# Sheet1.net
KiCad netlist of a schematic drawn in Altium Designer
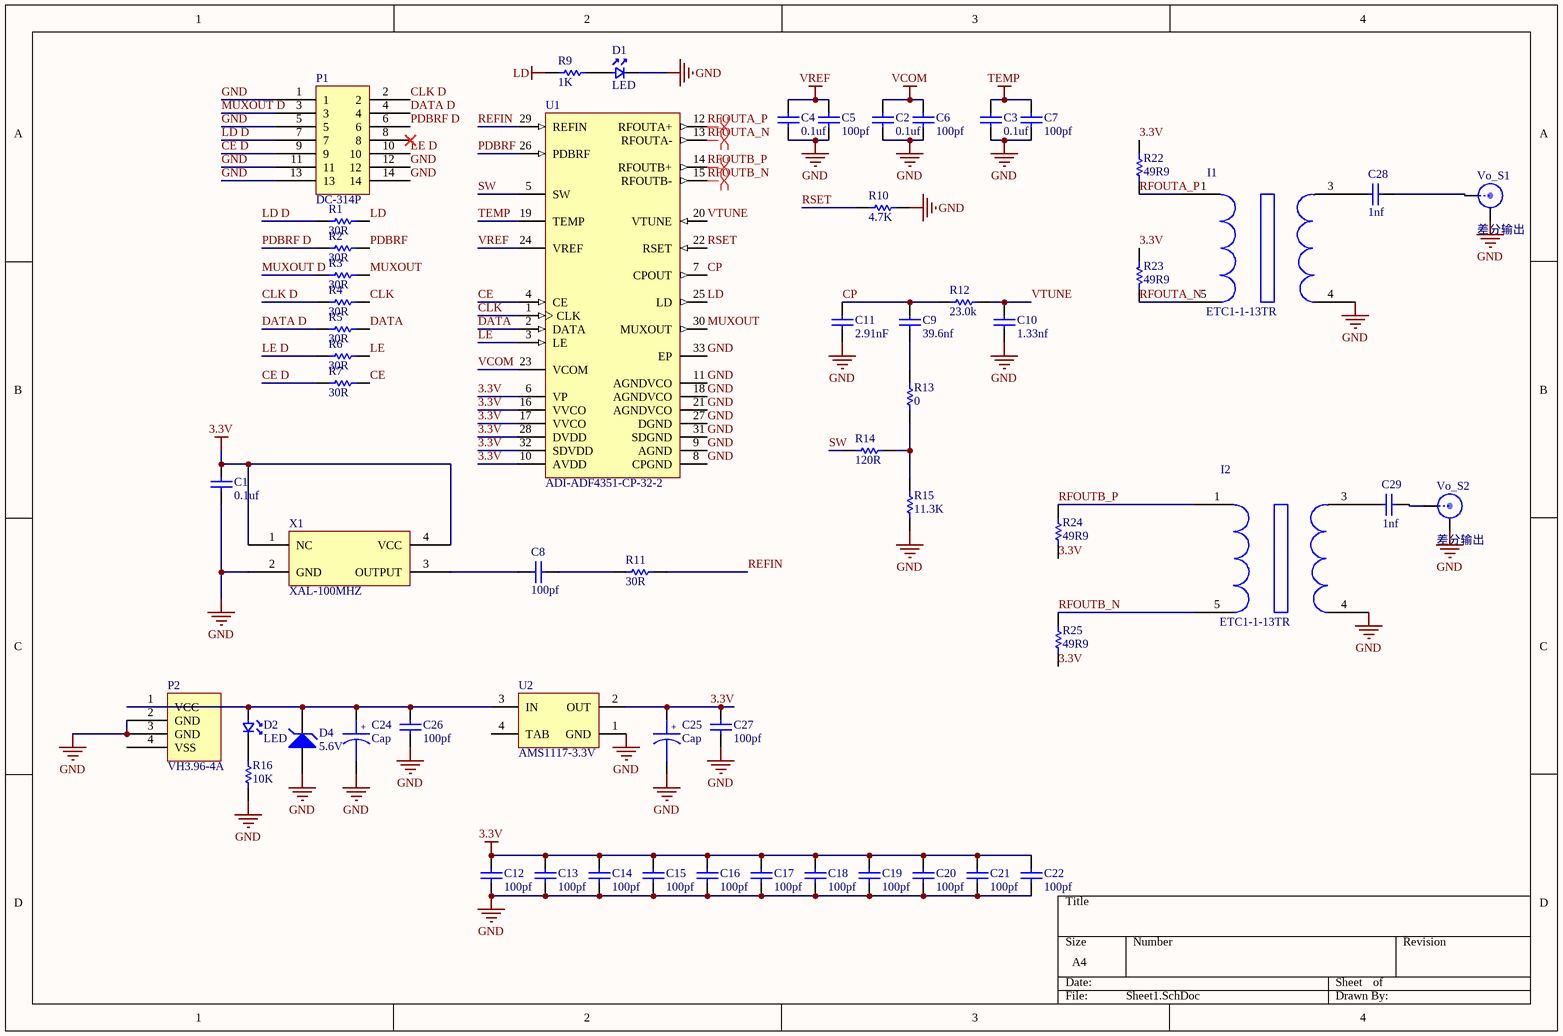
[diagram p0: Sheet1.SchDoc]

(export (version "E")
  (design (tool "Eeschema 10.0.6"))
  (components
    (comp (ref "C1") (value "0.1uf") (footprint "0805") (libsource (lib "Schlib1") (part "Cap")))
    (comp (ref "C2") (value "0.1uf") (footprint "0805") (libsource (lib "Schlib1") (part "Cap")))
    (comp (ref "C3") (value "0.1uf") (footprint "0805") (libsource (lib "Schlib1") (part "Cap")))
    (comp (ref "C4") (value "0.1uf") (footprint "0805") (libsource (lib "Schlib1") (part "Cap")))
    (comp (ref "C5") (value "100pf") (footprint "0805") (libsource (lib "Schlib1") (part "Cap")))
    (comp (ref "C6") (value "100pf") (footprint "0805") (libsource (lib "Schlib1") (part "Cap")))
    (comp (ref "C7") (value "100pf") (footprint "0805") (libsource (lib "Schlib1") (part "Cap")))
    (comp (ref "C8") (value "100pf") (footprint "0805") (libsource (lib "Schlib1") (part "Cap")))
    (comp (ref "C9") (value "39.6nf") (footprint "0805") (libsource (lib "Schlib1") (part "Cap")))
    (comp (ref "C10") (value "1.33nf") (footprint "0805") (libsource (lib "Schlib1") (part "Cap")))
    (comp (ref "C11") (value "2.91nF") (footprint "0805") (libsource (lib "Schlib1") (part "Cap")))
    (comp (ref "C12") (value "100pf") (footprint "0805") (libsource (lib "Schlib1") (part "Cap")))
    (comp (ref "C13") (value "100pf") (footprint "0805") (libsource (lib "Schlib1") (part "Cap")))
    (comp (ref "C14") (value "100pf") (footprint "0805") (libsource (lib "Schlib1") (part "Cap")))
    (comp (ref "C15") (value "100pf") (footprint "0805") (libsource (lib "Schlib1") (part "Cap")))
    (comp (ref "C16") (value "100pf") (footprint "0805") (libsource (lib "Schlib1") (part "Cap")))
    (comp (ref "C17") (value "100pf") (footprint "0805") (libsource (lib "Schlib1") (part "Cap")))
    (comp (ref "C18") (value "100pf") (footprint "0805") (libsource (lib "Schlib1") (part "Cap")))
    (comp (ref "C19") (value "100pf") (footprint "0805") (libsource (lib "Schlib1") (part "Cap")))
    (comp (ref "C20") (value "100pf") (footprint "0805") (libsource (lib "Schlib1") (part "Cap")))
    (comp (ref "C21") (value "100pf") (footprint "0805") (libsource (lib "Schlib1") (part "Cap")))
    (comp (ref "C22") (value "100pf") (footprint "0805") (libsource (lib "Schlib1") (part "Cap")))
    (comp (ref "C24")
      (value "Cap")
      (footprint "7343C-TYPE_D")
      (libsource (lib "Schlib1") (part "Tantalium Cap"))
    )
    (comp (ref "C25")
      (value "Cap")
      (footprint "7343C-TYPE_D")
      (libsource (lib "Schlib1") (part "Tantalium Cap"))
    )
    (comp (ref "C26") (value "100pf") (footprint "0805") (libsource (lib "Schlib1") (part "Cap")))
    (comp (ref "C27") (value "100pf") (footprint "0805") (libsource (lib "Schlib1") (part "Cap")))
    (comp (ref "C28") (value "1nf") (footprint "0805") (libsource (lib "Schlib1") (part "Cap")))
    (comp (ref "C29") (value "1nf") (footprint "0805") (libsource (lib "Schlib1") (part "Cap")))
    (comp (ref "D1") (value "LED") (footprint "0805_s") (libsource (lib "Schlib1") (part "LED")))
    (comp (ref "D2") (value "LED") (footprint "0805_s") (libsource (lib "Schlib1") (part "LED")))
    (comp (ref "D4") (value "5.6V") (footprint "SMA/DO-214AC") (libsource (lib "Schlib1") (part "肖特基-5.6V")))
    (comp (ref "I1")
      (value "ETC1-1-13TR")
      (footprint "SM-22")
      (libsource (lib "Schlib1") (part "ETC1-1-13TR"))
    )
    (comp (ref "I2")
      (value "ETC1-1-13TR")
      (footprint "SM-22")
      (libsource (lib "Schlib1") (part "ETC1-1-13TR"))
    )
    (comp (ref "P1") (value "DC-314P") (footprint "DC3-14P") (libsource (lib "Schlib1") (part "DC3-14P")))
    (comp (ref "P2")
      (value "VH3.96-4A")
      (footprint "VH3.96-4P")
      (libsource (lib "Schlib1") (part "VH3.96-4A"))
    )
    (comp (ref "R1") (value "30R") (footprint "0805") (libsource (lib "Schlib1") (part "Res")))
    (comp (ref "R2") (value "30R") (footprint "0805") (libsource (lib "Schlib1") (part "Res")))
    (comp (ref "R3") (value "30R") (footprint "0805") (libsource (lib "Schlib1") (part "Res")))
    (comp (ref "R4") (value "30R") (footprint "0805") (libsource (lib "Schlib1") (part "Res")))
    (comp (ref "R5") (value "30R") (footprint "0805") (libsource (lib "Schlib1") (part "Res")))
    (comp (ref "R6") (value "30R") (footprint "0805") (libsource (lib "Schlib1") (part "Res")))
    (comp (ref "R7") (value "30R") (footprint "0805") (libsource (lib "Schlib1") (part "Res")))
    (comp (ref "R9") (value "1K") (footprint "0805") (libsource (lib "Schlib1") (part "Res")))
    (comp (ref "R10") (value "4.7K") (footprint "0805") (libsource (lib "Schlib1") (part "Res")))
    (comp (ref "R11") (value "30R") (footprint "0805") (libsource (lib "Schlib1") (part "Res")))
    (comp (ref "R12") (value "23.0k") (footprint "0805") (libsource (lib "Schlib1") (part "Res")))
    (comp (ref "R13") (value "0") (footprint "0805") (libsource (lib "Schlib1") (part "Res")))
    (comp (ref "R14") (value "120R") (footprint "0805") (libsource (lib "Schlib1") (part "Res")))
    (comp (ref "R15") (value "11.3K") (footprint "0805") (libsource (lib "Schlib1") (part "Res")))
    (comp (ref "R16") (value "10K") (footprint "0805") (libsource (lib "Schlib1") (part "Res")))
    (comp (ref "R22") (value "49R9") (footprint "0805") (libsource (lib "Schlib1") (part "Res")))
    (comp (ref "R23") (value "49R9") (footprint "0805") (libsource (lib "Schlib1") (part "Res")))
    (comp (ref "R24") (value "49R9") (footprint "0805") (libsource (lib "Schlib1") (part "Res")))
    (comp (ref "R25") (value "49R9") (footprint "0805") (libsource (lib "Schlib1") (part "Res")))
    (comp (ref "U1")
      (value "ADI-ADF4351-CP-32-2")
      (footprint "ADI-CP-32-2_M")
      (libsource (lib "Schlib1") (part "ADI-ADF4351-CP-32-2"))
    )
    (comp (ref "U2")
      (value "AMS1117-3.3V")
      (footprint "SOT-223")
      (libsource (lib "Schlib1") (part "AMS1117-3.3V"))
    )
    (comp (ref "Vo_S1") (value "差分输出") (footprint "SMA-LYING") (libsource (lib "Schlib1") (part "SMA")))
    (comp (ref "Vo_S2") (value "差分输出") (footprint "SMA-LYING") (libsource (lib "Schlib1") (part "SMA")))
    (comp (ref "X1") (value "XAL-100MHZ") (footprint "SMD4_7050") (libsource (lib "Schlib1") (part "XAL")))
  )
  (nets
    (net (code "1") (name "/CE") (class "Default")
      (node (ref "R7") (pin "2") (pinfunction "2_2") (pintype "passive"))
      (node (ref "U1") (pin "4") (pinfunction "CE_4") (pintype "input"))
    )
    (net (code "2") (name "/CE D") (class "Default")
      (node (ref "P1") (pin "9") (pinfunction "9_9") (pintype "passive"))
      (node (ref "R7") (pin "1") (pinfunction "1_1") (pintype "passive"))
    )
    (net (code "3") (name "/CLK") (class "Default")
      (node (ref "R4") (pin "2") (pinfunction "2_2") (pintype "passive"))
      (node (ref "U1") (pin "1") (pinfunction "CLK_1") (pintype "input"))
    )
    (net (code "4") (name "/CLK D") (class "Default")
      (node (ref "P1") (pin "2") (pinfunction "2_2") (pintype "passive"))
      (node (ref "R4") (pin "1") (pinfunction "1_1") (pintype "passive"))
    )
    (net (code "5") (name "/CP") (class "Default")
      (node (ref "C11") (pin "2") (pinfunction "2_2") (pintype "passive"))
      (node (ref "C9") (pin "2") (pinfunction "2_2") (pintype "passive"))
      (node (ref "R12") (pin "1") (pinfunction "1_1") (pintype "passive"))
      (node (ref "U1") (pin "7") (pinfunction "CPOUT_7") (pintype "output"))
    )
    (net (code "6") (name "/DATA") (class "Default")
      (node (ref "R5") (pin "2") (pinfunction "2_2") (pintype "passive"))
      (node (ref "U1") (pin "2") (pinfunction "DATA_2") (pintype "input"))
    )
    (net (code "7") (name "/DATA D") (class "Default")
      (node (ref "P1") (pin "4") (pinfunction "4_4") (pintype "passive"))
      (node (ref "R5") (pin "1") (pinfunction "1_1") (pintype "passive"))
    )
    (net (code "8") (name "/LD D") (class "Default")
      (node (ref "P1") (pin "7") (pinfunction "7_7") (pintype "passive"))
      (node (ref "R1") (pin "1") (pinfunction "1_1") (pintype "passive"))
    )
    (net (code "9") (name "/LE") (class "Default")
      (node (ref "R6") (pin "2") (pinfunction "2_2") (pintype "passive"))
      (node (ref "U1") (pin "3") (pinfunction "LE_3") (pintype "input"))
    )
    (net (code "10") (name "/LE D") (class "Default")
      (node (ref "P1") (pin "10") (pinfunction "10_10") (pintype "passive"))
      (node (ref "R6") (pin "1") (pinfunction "1_1") (pintype "passive"))
    )
    (net (code "11") (name "/MUXOUT") (class "Default")
      (node (ref "R3") (pin "2") (pinfunction "2_2") (pintype "passive"))
      (node (ref "U1") (pin "30") (pinfunction "MUXOUT_30") (pintype "output"))
    )
    (net (code "12") (name "/MUXOUT D") (class "Default")
      (node (ref "P1") (pin "3") (pinfunction "3_3") (pintype "passive"))
      (node (ref "R3") (pin "1") (pinfunction "1_1") (pintype "passive"))
    )
    (net (code "13") (name "/PDBRF") (class "Default")
      (node (ref "R2") (pin "2") (pinfunction "2_2") (pintype "passive"))
      (node (ref "U1") (pin "26") (pinfunction "PDBRF_26") (pintype "input"))
    )
    (net (code "14") (name "/PDBRF D") (class "Default")
      (node (ref "P1") (pin "6") (pinfunction "6_6") (pintype "passive"))
      (node (ref "R2") (pin "1") (pinfunction "1_1") (pintype "passive"))
    )
    (net (code "15") (name "/REFIN") (class "Default")
      (node (ref "R11") (pin "1") (pinfunction "1_1") (pintype "passive"))
      (node (ref "U1") (pin "29") (pinfunction "REFIN_29") (pintype "input"))
    )
    (net (code "16") (name "/RFOUTA_N") (class "Default")
      (node (ref "I1") (pin "5") (pinfunction "5_5") (pintype "passive"))
      (node (ref "R23") (pin "2") (pinfunction "2_2") (pintype "passive"))
      (node (ref "U1") (pin "13") (pinfunction "RFOUTA-_13") (pintype "output"))
    )
    (net (code "17") (name "/RFOUTA_P") (class "Default")
      (node (ref "I1") (pin "1") (pinfunction "1_1") (pintype "passive"))
      (node (ref "R22") (pin "1") (pinfunction "1_1") (pintype "passive"))
      (node (ref "U1") (pin "12") (pinfunction "RFOUTA+_12") (pintype "output"))
    )
    (net (code "18") (name "/RFOUTB_N") (class "Default")
      (node (ref "I2") (pin "5") (pinfunction "5_5") (pintype "passive"))
      (node (ref "R25") (pin "2") (pinfunction "2_2") (pintype "passive"))
      (node (ref "U1") (pin "15") (pinfunction "RFOUTB-_15") (pintype "output"))
    )
    (net (code "19") (name "/RFOUTB_P") (class "Default")
      (node (ref "I2") (pin "1") (pinfunction "1_1") (pintype "passive"))
      (node (ref "R24") (pin "2") (pinfunction "2_2") (pintype "passive"))
      (node (ref "U1") (pin "14") (pinfunction "RFOUTB+_14") (pintype "output"))
    )
    (net (code "20") (name "/RSET") (class "Default")
      (node (ref "R10") (pin "1") (pinfunction "1_1") (pintype "passive"))
      (node (ref "U1") (pin "22") (pinfunction "RSET_22") (pintype "input"))
    )
    (net (code "21") (name "/SW") (class "Default")
      (node (ref "R14") (pin "2") (pinfunction "2_2") (pintype "passive"))
      (node (ref "U1") (pin "5") (pinfunction "SW_5") (pintype "passive"))
    )
    (net (code "22") (name "/VTUNE") (class "Default")
      (node (ref "C10") (pin "2") (pinfunction "2_2") (pintype "passive"))
      (node (ref "R12") (pin "2") (pinfunction "2_2") (pintype "passive"))
      (node (ref "U1") (pin "20") (pinfunction "VTUNE_20") (pintype "input"))
    )
    (net (code "23") (name "3.3V") (class "Default")
      (node (ref "C1") (pin "2") (pinfunction "2_2") (pintype "passive"))
      (node (ref "C12") (pin "2") (pinfunction "2_2") (pintype "passive"))
      (node (ref "C13") (pin "2") (pinfunction "2_2") (pintype "passive"))
      (node (ref "C14") (pin "2") (pinfunction "2_2") (pintype "passive"))
      (node (ref "C15") (pin "2") (pinfunction "2_2") (pintype "passive"))
      (node (ref "C16") (pin "2") (pinfunction "2_2") (pintype "passive"))
      (node (ref "C17") (pin "2") (pinfunction "2_2") (pintype "passive"))
      (node (ref "C18") (pin "2") (pinfunction "2_2") (pintype "passive"))
      (node (ref "C19") (pin "2") (pinfunction "2_2") (pintype "passive"))
      (node (ref "C20") (pin "2") (pinfunction "2_2") (pintype "passive"))
      (node (ref "C21") (pin "2") (pinfunction "2_2") (pintype "passive"))
      (node (ref "C22") (pin "2") (pinfunction "2_2") (pintype "passive"))
      (node (ref "C25") (pin "1") (pinfunction "1_1") (pintype "passive"))
      (node (ref "C27") (pin "2") (pinfunction "2_2") (pintype "passive"))
      (node (ref "R22") (pin "2") (pinfunction "2_2") (pintype "passive"))
      (node (ref "R23") (pin "1") (pinfunction "1_1") (pintype "passive"))
      (node (ref "R24") (pin "1") (pinfunction "1_1") (pintype "passive"))
      (node (ref "R25") (pin "1") (pinfunction "1_1") (pintype "passive"))
      (node (ref "U1") (pin "10") (pinfunction "AVDD_10") (pintype "power_in"))
      (node (ref "U1") (pin "16") (pinfunction "VVCO_16") (pintype "power_in"))
      (node (ref "U1") (pin "17") (pinfunction "VVCO_17") (pintype "power_in"))
      (node (ref "U1") (pin "28") (pinfunction "DVDD_28") (pintype "power_in"))
      (node (ref "U1") (pin "32") (pinfunction "SDVDD_32") (pintype "power_in"))
      (node (ref "U1") (pin "6") (pinfunction "VP_6") (pintype "power_in"))
      (node (ref "U2") (pin "2") (pinfunction "OUT_2") (pintype "power_in"))
      (node (ref "X1") (pin "1") (pinfunction "NC_1") (pintype "passive"))
      (node (ref "X1") (pin "4") (pinfunction "VCC_4") (pintype "passive"))
    )
    (net (code "24") (name "GND") (class "Default")
      (node (ref "C1") (pin "1") (pinfunction "1_1") (pintype "passive"))
      (node (ref "C10") (pin "1") (pinfunction "1_1") (pintype "passive"))
      (node (ref "C11") (pin "1") (pinfunction "1_1") (pintype "passive"))
      (node (ref "C12") (pin "1") (pinfunction "1_1") (pintype "passive"))
      (node (ref "C13") (pin "1") (pinfunction "1_1") (pintype "passive"))
      (node (ref "C14") (pin "1") (pinfunction "1_1") (pintype "passive"))
      (node (ref "C15") (pin "1") (pinfunction "1_1") (pintype "passive"))
      (node (ref "C16") (pin "1") (pinfunction "1_1") (pintype "passive"))
      (node (ref "C17") (pin "1") (pinfunction "1_1") (pintype "passive"))
      (node (ref "C18") (pin "1") (pinfunction "1_1") (pintype "passive"))
      (node (ref "C19") (pin "1") (pinfunction "1_1") (pintype "passive"))
      (node (ref "C2") (pin "1") (pinfunction "1_1") (pintype "passive"))
      (node (ref "C20") (pin "1") (pinfunction "1_1") (pintype "passive"))
      (node (ref "C21") (pin "1") (pinfunction "1_1") (pintype "passive"))
      (node (ref "C22") (pin "1") (pinfunction "1_1") (pintype "passive"))
      (node (ref "C24") (pin "2") (pinfunction "2_2") (pintype "passive"))
      (node (ref "C25") (pin "2") (pinfunction "2_2") (pintype "passive"))
      (node (ref "C26") (pin "1") (pinfunction "1_1") (pintype "passive"))
      (node (ref "C27") (pin "1") (pinfunction "1_1") (pintype "passive"))
      (node (ref "C3") (pin "1") (pinfunction "1_1") (pintype "passive"))
      (node (ref "C4") (pin "1") (pinfunction "1_1") (pintype "passive"))
      (node (ref "C5") (pin "1") (pinfunction "1_1") (pintype "passive"))
      (node (ref "C6") (pin "1") (pinfunction "1_1") (pintype "passive"))
      (node (ref "C7") (pin "1") (pinfunction "1_1") (pintype "passive"))
      (node (ref "D1") (pin "1") (pinfunction "1_1") (pintype "passive"))
      (node (ref "D4") (pin "1") (pinfunction "A_1") (pintype "passive"))
      (node (ref "I1") (pin "4") (pinfunction "4_4") (pintype "passive"))
      (node (ref "I2") (pin "4") (pinfunction "4_4") (pintype "passive"))
      (node (ref "P1") (pin "1") (pinfunction "1_1") (pintype "passive"))
      (node (ref "P1") (pin "11") (pinfunction "11_11") (pintype "passive"))
      (node (ref "P1") (pin "12") (pinfunction "12_12") (pintype "passive"))
      (node (ref "P1") (pin "13") (pinfunction "13_13") (pintype "passive"))
      (node (ref "P1") (pin "14") (pinfunction "14_14") (pintype "passive"))
      (node (ref "P1") (pin "5") (pinfunction "5_5") (pintype "passive"))
      (node (ref "P2") (pin "2") (pinfunction "GND_2") (pintype "passive"))
      (node (ref "P2") (pin "3") (pinfunction "GND_3") (pintype "passive"))
      (node (ref "R10") (pin "2") (pinfunction "2_2") (pintype "passive"))
      (node (ref "R15") (pin "2") (pinfunction "2_2") (pintype "passive"))
      (node (ref "R16") (pin "1") (pinfunction "1_1") (pintype "passive"))
      (node (ref "U1") (pin "11") (pinfunction "AGNDVCO_11") (pintype "power_in"))
      (node (ref "U1") (pin "18") (pinfunction "AGNDVCO_18") (pintype "power_in"))
      (node (ref "U1") (pin "21") (pinfunction "AGNDVCO_21") (pintype "power_in"))
      (node (ref "U1") (pin "27") (pinfunction "DGND_27") (pintype "power_in"))
      (node (ref "U1") (pin "31") (pinfunction "SDGND_31") (pintype "power_in"))
      (node (ref "U1") (pin "33") (pinfunction "EP_33") (pintype "power_in"))
      (node (ref "U1") (pin "8") (pinfunction "CPGND_8") (pintype "power_in"))
      (node (ref "U1") (pin "9") (pinfunction "AGND_9") (pintype "power_in"))
      (node (ref "U2") (pin "1") (pinfunction "GND_1") (pintype "power_in"))
      (node (ref "Vo_S1") (pin "1") (pinfunction "1_1") (pintype "passive"))
      (node (ref "Vo_S2") (pin "1") (pinfunction "1_1") (pintype "passive"))
      (node (ref "X1") (pin "2") (pinfunction "GND_2") (pintype "passive"))
    )
    (net (code "25") (name "LD") (class "Default")
      (node (ref "R1") (pin "2") (pinfunction "2_2") (pintype "passive"))
      (node (ref "R9") (pin "1") (pinfunction "1_1") (pintype "passive"))
      (node (ref "U1") (pin "25") (pinfunction "LD_25") (pintype "output"))
    )
    (net (code "26") (name "Net-(C8-Pad1)") (class "Default")
      (node (ref "C8") (pin "1") (pinfunction "1_1") (pintype "passive"))
      (node (ref "R11") (pin "2") (pinfunction "2_2") (pintype "passive"))
    )
    (net (code "27") (name "Net-(C9-Pad1)") (class "Default")
      (node (ref "C9") (pin "1") (pinfunction "1_1") (pintype "passive"))
      (node (ref "R13") (pin "2") (pinfunction "2_2") (pintype "passive"))
    )
    (net (code "28") (name "Net-(C28-Pad1)") (class "Default")
      (node (ref "C28") (pin "1") (pinfunction "1_1") (pintype "passive"))
      (node (ref "I1") (pin "3") (pinfunction "3_3") (pintype "passive"))
    )
    (net (code "29") (name "Net-(C28-Pad2)") (class "Default")
      (node (ref "C28") (pin "2") (pinfunction "2_2") (pintype "passive"))
      (node (ref "Vo_S1") (pin "0") (pinfunction "0_0") (pintype "passive"))
    )
    (net (code "30") (name "Net-(C29-Pad1)") (class "Default")
      (node (ref "C29") (pin "1") (pinfunction "1_1") (pintype "passive"))
      (node (ref "I2") (pin "3") (pinfunction "3_3") (pintype "passive"))
    )
    (net (code "31") (name "Net-(C29-Pad2)") (class "Default")
      (node (ref "C29") (pin "2") (pinfunction "2_2") (pintype "passive"))
      (node (ref "Vo_S2") (pin "0") (pinfunction "0_0") (pintype "passive"))
    )
    (net (code "32") (name "Net-(D1-Pad2)") (class "Default")
      (node (ref "D1") (pin "2") (pinfunction "2_2") (pintype "passive"))
      (node (ref "R9") (pin "2") (pinfunction "2_2") (pintype "passive"))
    )
    (net (code "33") (name "Net-(D2-Pad1)") (class "Default")
      (node (ref "D2") (pin "1") (pinfunction "1_1") (pintype "passive"))
      (node (ref "R16") (pin "2") (pinfunction "2_2") (pintype "passive"))
    )
    (net (code "34") (name "Net-(D4-K)") (class "Default")
      (node (ref "C24") (pin "1") (pinfunction "1_1") (pintype "passive"))
      (node (ref "C26") (pin "2") (pinfunction "2_2") (pintype "passive"))
      (node (ref "D2") (pin "2") (pinfunction "2_2") (pintype "passive"))
      (node (ref "D4") (pin "2") (pinfunction "K_2") (pintype "passive"))
      (node (ref "P2") (pin "1") (pinfunction "VCC_1") (pintype "passive"))
      (node (ref "U2") (pin "3") (pinfunction "IN_3") (pintype "power_in"))
    )
    (net (code "35") (name "Net-(R13-Pad1)") (class "Default")
      (node (ref "R13") (pin "1") (pinfunction "1_1") (pintype "passive"))
      (node (ref "R14") (pin "1") (pinfunction "1_1") (pintype "passive"))
      (node (ref "R15") (pin "1") (pinfunction "1_1") (pintype "passive"))
    )
    (net (code "36") (name "Net-(X1-OUTPUT)") (class "Default")
      (node (ref "C8") (pin "2") (pinfunction "2_2") (pintype "passive"))
      (node (ref "X1") (pin "3") (pinfunction "OUTPUT_3") (pintype "passive"))
    )
    (net (code "37") (name "TEMP") (class "Default")
      (node (ref "C3") (pin "2") (pinfunction "2_2") (pintype "passive"))
      (node (ref "C7") (pin "2") (pinfunction "2_2") (pintype "passive"))
      (node (ref "U1") (pin "19") (pinfunction "TEMP_19") (pintype "passive"))
    )
    (net (code "38") (name "VCOM") (class "Default")
      (node (ref "C2") (pin "2") (pinfunction "2_2") (pintype "passive"))
      (node (ref "C6") (pin "2") (pinfunction "2_2") (pintype "passive"))
      (node (ref "U1") (pin "23") (pinfunction "VCOM_23") (pintype "passive"))
    )
    (net (code "39") (name "VREF") (class "Default")
      (node (ref "C4") (pin "2") (pinfunction "2_2") (pintype "passive"))
      (node (ref "C5") (pin "2") (pinfunction "2_2") (pintype "passive"))
      (node (ref "U1") (pin "24") (pinfunction "VREF_24") (pintype "passive"))
    )
    (net (code "40") (name "unconnected-(P1-Pad8)") (class "Default")
      (node (ref "P1") (pin "8") (pinfunction "8_8") (pintype "passive+no_connect"))
    )
    (net (code "41") (name "unconnected-(P2-VSS-Pad4)") (class "Default")
      (node (ref "P2") (pin "4") (pinfunction "VSS_4") (pintype "passive"))
    )
    (net (code "42") (name "unconnected-(U2-TAB-Pad4)") (class "Default")
      (node (ref "U2") (pin "4") (pinfunction "TAB_4") (pintype "power_in"))
    )
  )
)
